# lofisampler.net
KiCad netlist of a schematic drawn in EAGLE
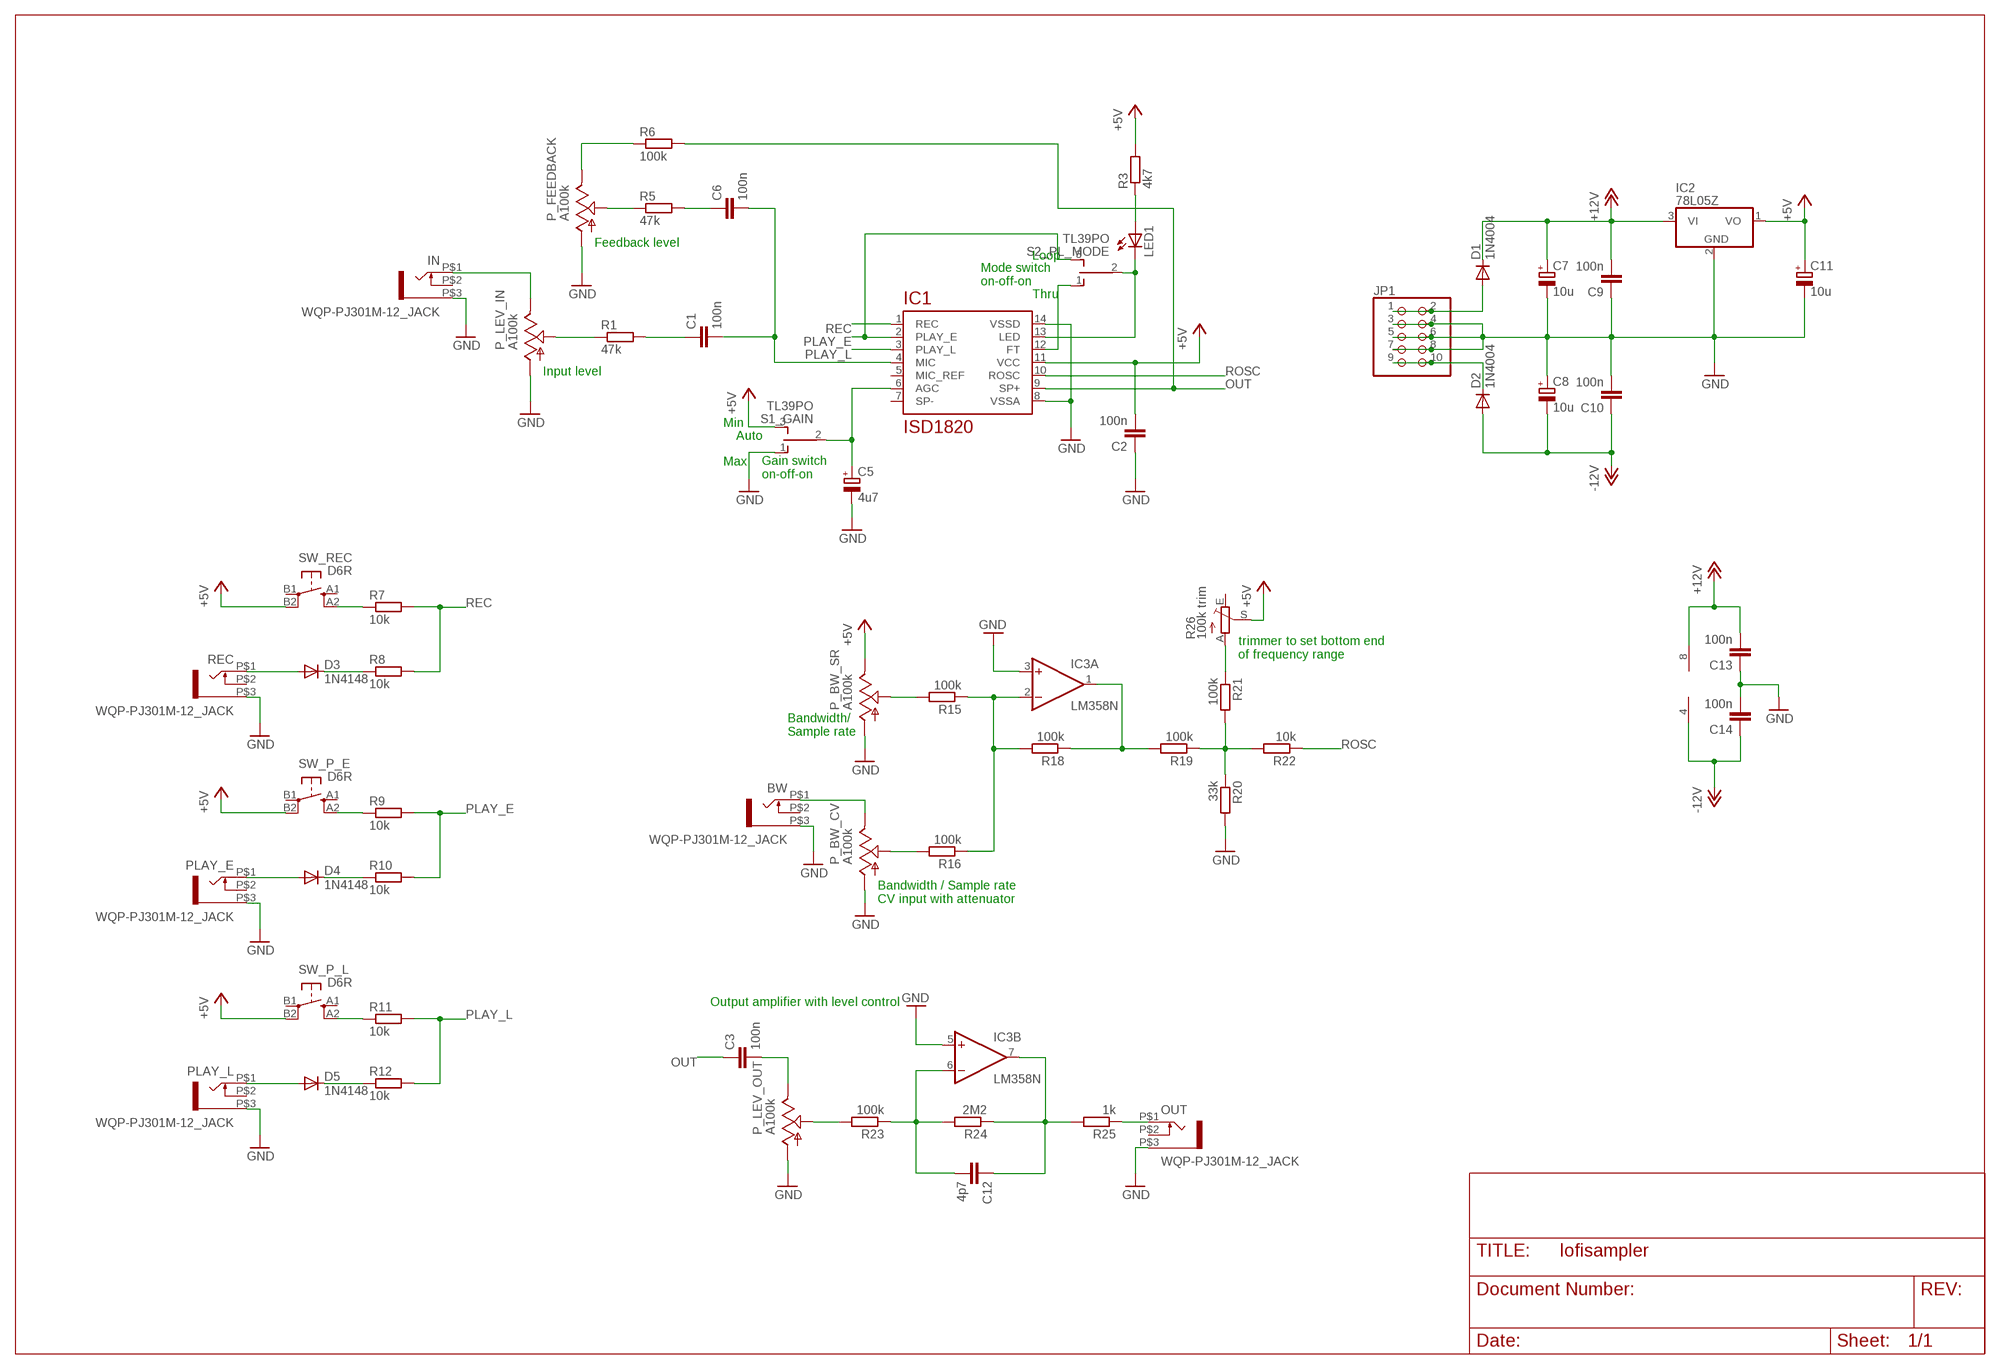
[diagram p0: schematic, sheet 1]

(export (version "E")
  (design (tool "Eeschema 10.0.6"))
  (components
    (comp (ref "BW")
      (value "WQP-PJ301M-12_JACK")
      (footprint "eagle-import:WQP-PJ301M-12_JACK")
      (libsource (lib "eagle-import") (part "WQP-PJ301M-12_JACK"))
    )
    (comp (ref "C1")
      (value "100n")
      (footprint "eagle-import:C050-025X075")
      (libsource (lib "eagle-import") (part "C-EU050-025X075"))
    )
    (comp (ref "C2")
      (value "100n")
      (footprint "eagle-import:C025-025X050")
      (libsource (lib "eagle-import") (part "C-EU025-025X050"))
    )
    (comp (ref "C3")
      (value "100n")
      (footprint "eagle-import:C050-025X075")
      (libsource (lib "eagle-import") (part "C-EU050-025X075"))
    )
    (comp (ref "C5")
      (value "4u7")
      (footprint "eagle-import:E2,5-5")
      (libsource (lib "eagle-import") (part "CPOL-EUE2.5-5"))
    )
    (comp (ref "C6")
      (value "100n")
      (footprint "eagle-import:C050-025X075")
      (libsource (lib "eagle-import") (part "C-EU050-025X075"))
    )
    (comp (ref "C7")
      (value "10u")
      (footprint "eagle-import:E2,5-5")
      (libsource (lib "eagle-import") (part "CPOL-EUE2.5-5"))
    )
    (comp (ref "C8")
      (value "10u")
      (footprint "eagle-import:E2,5-5")
      (libsource (lib "eagle-import") (part "CPOL-EUE2.5-5"))
    )
    (comp (ref "C9")
      (value "100n")
      (footprint "eagle-import:C025-025X050")
      (libsource (lib "eagle-import") (part "C-EU025-025X050"))
    )
    (comp (ref "C10")
      (value "100n")
      (footprint "eagle-import:C025-025X050")
      (libsource (lib "eagle-import") (part "C-EU025-025X050"))
    )
    (comp (ref "C11")
      (value "10u")
      (footprint "eagle-import:E2,5-5")
      (libsource (lib "eagle-import") (part "CPOL-EUE2.5-5"))
    )
    (comp (ref "C12")
      (value "4p7")
      (footprint "eagle-import:C025-025X050")
      (libsource (lib "eagle-import") (part "C-EU025-025X050"))
    )
    (comp (ref "C13")
      (value "100n")
      (footprint "eagle-import:C025-025X050")
      (libsource (lib "eagle-import") (part "C-EU025-025X050"))
    )
    (comp (ref "C14")
      (value "100n")
      (footprint "eagle-import:C025-025X050")
      (libsource (lib "eagle-import") (part "C-EU025-025X050"))
    )
    (comp (ref "D1")
      (value "1N4004")
      (footprint "eagle-import:DO41-10")
      (libsource (lib "eagle-import") (part "1N4004"))
    )
    (comp (ref "D2")
      (value "1N4004")
      (footprint "eagle-import:DO41-10")
      (libsource (lib "eagle-import") (part "1N4004"))
    )
    (comp (ref "D3")
      (value "1N4148")
      (footprint "eagle-import:DO35-7")
      (libsource (lib "eagle-import") (part "1N4148DO35-7"))
    )
    (comp (ref "D4")
      (value "1N4148")
      (footprint "eagle-import:DO35-7")
      (libsource (lib "eagle-import") (part "1N4148DO35-7"))
    )
    (comp (ref "D5")
      (value "1N4148")
      (footprint "eagle-import:DO35-7")
      (libsource (lib "eagle-import") (part "1N4148DO35-7"))
    )
    (comp (ref "IC1")
      (value "ISD1820")
      (footprint "eagle-import:DIL14")
      (libsource (lib "eagle-import") (part "ISD1820"))
    )
    (comp (ref "IC2")
      (value "78L05Z")
      (footprint "eagle-import:TO92")
      (libsource (lib "eagle-import") (part "78ZL05"))
    )
    (comp (ref "IC3")
      (value "LM358N")
      (footprint "eagle-import:DIL08")
      (libsource (lib "eagle-import") (part "LM358N"))
    )
    (comp (ref "IN")
      (value "WQP-PJ301M-12_JACK")
      (footprint "eagle-import:WQP-PJ301M-12_JACK")
      (libsource (lib "eagle-import") (part "WQP-PJ301M-12_JACK"))
    )
    (comp (ref "JP1")
      (value "PINHD-2X5")
      (footprint "eagle-import:2X05")
      (libsource (lib "eagle-import") (part "PINHD-2X5"))
    )
    (comp (ref "LED1")
      (value "LED5MM")
      (footprint "eagle-import:LED5MM")
      (libsource (lib "eagle-import") (part "LED5MM"))
    )
    (comp (ref "OUT")
      (value "WQP-PJ301M-12_JACK")
      (footprint "eagle-import:WQP-PJ301M-12_JACK")
      (libsource (lib "eagle-import") (part "WQP-PJ301M-12_JACK"))
    )
    (comp (ref "PLAY_E")
      (value "WQP-PJ301M-12_JACK")
      (footprint "eagle-import:WQP-PJ301M-12_JACK")
      (libsource (lib "eagle-import") (part "WQP-PJ301M-12_JACK"))
    )
    (comp (ref "PLAY_L")
      (value "WQP-PJ301M-12_JACK")
      (footprint "eagle-import:WQP-PJ301M-12_JACK")
      (libsource (lib "eagle-import") (part "WQP-PJ301M-12_JACK"))
    )
    (comp (ref "P_BW_CV")
      (value "A100k")
      (footprint "eagle-import:ALPS_POT_VERTICAL")
      (libsource (lib "eagle-import") (part "POT_USVERTICAL"))
    )
    (comp (ref "P_BW_SR")
      (value "A100k")
      (footprint "eagle-import:ALPS_POT_VERTICAL")
      (libsource (lib "eagle-import") (part "POT_USVERTICAL"))
    )
    (comp (ref "P_FEEDBACK")
      (value "A100k")
      (footprint "eagle-import:ALPS_POT_VERTICAL")
      (libsource (lib "eagle-import") (part "POT_USVERTICAL"))
    )
    (comp (ref "P_LEV_IN")
      (value "A100k")
      (footprint "eagle-import:ALPS_POT_VERTICAL")
      (libsource (lib "eagle-import") (part "POT_USVERTICAL"))
    )
    (comp (ref "P_LEV_OUT")
      (value "A100k")
      (footprint "eagle-import:ALPS_POT_VERTICAL")
      (libsource (lib "eagle-import") (part "POT_USVERTICAL"))
    )
    (comp (ref "R1")
      (value "47k")
      (footprint "eagle-import:0207_2V")
      (libsource (lib "eagle-import") (part "R-EU_0207/2V"))
    )
    (comp (ref "R3")
      (value "4k7")
      (footprint "eagle-import:0207_2V")
      (libsource (lib "eagle-import") (part "R-EU_0207/2V"))
    )
    (comp (ref "R5")
      (value "47k")
      (footprint "eagle-import:0207_2V")
      (libsource (lib "eagle-import") (part "R-EU_0207/2V"))
    )
    (comp (ref "R6")
      (value "100k")
      (footprint "eagle-import:0207_2V")
      (libsource (lib "eagle-import") (part "R-EU_0207/2V"))
    )
    (comp (ref "R7")
      (value "10k")
      (footprint "eagle-import:0207_2V")
      (libsource (lib "eagle-import") (part "R-EU_0207/2V"))
    )
    (comp (ref "R8")
      (value "10k")
      (footprint "eagle-import:0207_2V")
      (libsource (lib "eagle-import") (part "R-EU_0207/2V"))
    )
    (comp (ref "R9")
      (value "10k")
      (footprint "eagle-import:0207_2V")
      (libsource (lib "eagle-import") (part "R-EU_0207/2V"))
    )
    (comp (ref "R10")
      (value "10k")
      (footprint "eagle-import:0207_2V")
      (libsource (lib "eagle-import") (part "R-EU_0207/2V"))
    )
    (comp (ref "R11")
      (value "10k")
      (footprint "eagle-import:0207_2V")
      (libsource (lib "eagle-import") (part "R-EU_0207/2V"))
    )
    (comp (ref "R12")
      (value "10k")
      (footprint "eagle-import:0207_2V")
      (libsource (lib "eagle-import") (part "R-EU_0207/2V"))
    )
    (comp (ref "R15")
      (value "100k")
      (footprint "eagle-import:0207_2V")
      (libsource (lib "eagle-import") (part "R-EU_0207/2V"))
    )
    (comp (ref "R16")
      (value "100k")
      (footprint "eagle-import:0207_2V")
      (libsource (lib "eagle-import") (part "R-EU_0207/2V"))
    )
    (comp (ref "R18")
      (value "100k")
      (footprint "eagle-import:0207_2V")
      (libsource (lib "eagle-import") (part "R-EU_0207/2V"))
    )
    (comp (ref "R19")
      (value "100k")
      (footprint "eagle-import:0207_2V")
      (libsource (lib "eagle-import") (part "R-EU_0207/2V"))
    )
    (comp (ref "R20")
      (value "33k")
      (footprint "eagle-import:0207_2V")
      (libsource (lib "eagle-import") (part "R-EU_0207/2V"))
    )
    (comp (ref "R21")
      (value "100k")
      (footprint "eagle-import:0207_2V")
      (libsource (lib "eagle-import") (part "R-EU_0207/2V"))
    )
    (comp (ref "R22")
      (value "10k")
      (footprint "eagle-import:0207_2V")
      (libsource (lib "eagle-import") (part "R-EU_0207/2V"))
    )
    (comp (ref "R23")
      (value "100k")
      (footprint "eagle-import:0207_2V")
      (libsource (lib "eagle-import") (part "R-EU_0207/2V"))
    )
    (comp (ref "R24")
      (value "2M2")
      (footprint "eagle-import:0207_2V")
      (libsource (lib "eagle-import") (part "R-EU_0207/2V"))
    )
    (comp (ref "R25")
      (value "1k")
      (footprint "eagle-import:0207_2V")
      (libsource (lib "eagle-import") (part "R-EU_0207/2V"))
    )
    (comp (ref "R26")
      (value "100k trim")
      (footprint "eagle-import:B25P")
      (libsource (lib "eagle-import") (part "TRIM_EU-B25P"))
    )
    (comp (ref "REC")
      (value "WQP-PJ301M-12_JACK")
      (footprint "eagle-import:WQP-PJ301M-12_JACK")
      (libsource (lib "eagle-import") (part "WQP-PJ301M-12_JACK"))
    )
    (comp (ref "S1_GAIN")
      (value "TL39PO")
      (footprint "eagle-import:TL3XPO")
      (libsource (lib "eagle-import") (part "TL39PO"))
    )
    (comp (ref "S2_PL_MODE")
      (value "TL39PO")
      (footprint "eagle-import:TL3XPO")
      (libsource (lib "eagle-import") (part "TL39PO"))
    )
    (comp (ref "SW_P_E")
      (value "D6R")
      (footprint "eagle-import:D6R")
      (libsource (lib "eagle-import") (part "D6R"))
    )
    (comp (ref "SW_P_L")
      (value "D6R")
      (footprint "eagle-import:D6R")
      (libsource (lib "eagle-import") (part "D6R"))
    )
    (comp (ref "SW_REC")
      (value "D6R")
      (footprint "eagle-import:D6R")
      (libsource (lib "eagle-import") (part "D6R"))
    )
  )
  (nets
    (net (code "1") (name "+5V") (class "Default")
      (node (ref "C11") (pin "+") (pinfunction "+_+") (pintype "passive"))
      (node (ref "C2") (pin "2") (pinfunction "2_2") (pintype "passive"))
      (node (ref "IC1") (pin "11") (pinfunction "VCC_11") (pintype "power_in"))
      (node (ref "IC2") (pin "1") (pinfunction "VO_1") (pintype "passive"))
      (node (ref "P_BW_SR") (pin "P$1") (pinfunction "E_P$1") (pintype "passive"))
      (node (ref "R26") (pin "S") (pinfunction "S_S") (pintype "passive"))
      (node (ref "R3") (pin "2") (pinfunction "2_2") (pintype "passive"))
      (node (ref "S1_GAIN") (pin "3") (pinfunction "S_3") (pintype "passive"))
      (node (ref "SW_P_E") (pin "B2") (pinfunction "P1_B2") (pintype "passive"))
      (node (ref "SW_P_L") (pin "B2") (pinfunction "P1_B2") (pintype "passive"))
      (node (ref "SW_REC") (pin "B2") (pinfunction "P1_B2") (pintype "passive"))
    )
    (net (code "2") (name "+12V") (class "Default")
      (node (ref "C13") (pin "2") (pinfunction "2_2") (pintype "passive"))
      (node (ref "C7") (pin "+") (pinfunction "+_+") (pintype "passive"))
      (node (ref "C9") (pin "2") (pinfunction "2_2") (pintype "passive"))
      (node (ref "D1") (pin "C") (pinfunction "C_C") (pintype "passive"))
      (node (ref "IC2") (pin "3") (pinfunction "VI_3") (pintype "input"))
      (node (ref "IC3") (pin "8") (pinfunction "V+_8") (pintype "power_in"))
    )
    (net (code "3") (name "-12V") (class "Default")
      (node (ref "C10") (pin "1") (pinfunction "1_1") (pintype "passive"))
      (node (ref "C14") (pin "1") (pinfunction "1_1") (pintype "passive"))
      (node (ref "C8") (pin "-") (pinfunction "-_-") (pintype "passive"))
      (node (ref "D2") (pin "A") (pinfunction "A_A") (pintype "passive"))
      (node (ref "IC3") (pin "4") (pinfunction "V-_4") (pintype "power_in"))
    )
    (net (code "4") (name "/OUT") (class "Default")
      (node (ref "C3") (pin "1") (pinfunction "1_1") (pintype "passive"))
      (node (ref "IC1") (pin "9") (pinfunction "SP+_9") (pintype "bidirectional"))
      (node (ref "R6") (pin "2") (pinfunction "2_2") (pintype "passive"))
    )
    (net (code "5") (name "/PLAY_E") (class "Default")
      (node (ref "IC1") (pin "2") (pinfunction "PLAY_E_2") (pintype "bidirectional"))
      (node (ref "R10") (pin "2") (pinfunction "2_2") (pintype "passive"))
      (node (ref "R9") (pin "2") (pinfunction "2_2") (pintype "passive"))
      (node (ref "S2_PL_MODE") (pin "3") (pinfunction "S_3") (pintype "passive"))
    )
    (net (code "6") (name "/PLAY_L") (class "Default")
      (node (ref "IC1") (pin "3") (pinfunction "PLAY_L_3") (pintype "bidirectional"))
      (node (ref "R11") (pin "2") (pinfunction "2_2") (pintype "passive"))
      (node (ref "R12") (pin "2") (pinfunction "2_2") (pintype "passive"))
    )
    (net (code "7") (name "/REC") (class "Default")
      (node (ref "IC1") (pin "1") (pinfunction "REC_1") (pintype "bidirectional"))
      (node (ref "R7") (pin "2") (pinfunction "2_2") (pintype "passive"))
      (node (ref "R8") (pin "2") (pinfunction "2_2") (pintype "passive"))
    )
    (net (code "8") (name "/ROSC") (class "Default")
      (node (ref "IC1") (pin "10") (pinfunction "ROSC_10") (pintype "bidirectional"))
      (node (ref "R22") (pin "1") (pinfunction "1_1") (pintype "passive"))
    )
    (net (code "9") (name "GND") (class "Default")
      (node (ref "BW") (pin "P$3") (pinfunction "1_P$3") (pintype "passive"))
      (node (ref "C10") (pin "2") (pinfunction "2_2") (pintype "passive"))
      (node (ref "C11") (pin "-") (pinfunction "-_-") (pintype "passive"))
      (node (ref "C13") (pin "1") (pinfunction "1_1") (pintype "passive"))
      (node (ref "C14") (pin "2") (pinfunction "2_2") (pintype "passive"))
      (node (ref "C2") (pin "1") (pinfunction "1_1") (pintype "passive"))
      (node (ref "C5") (pin "-") (pinfunction "-_-") (pintype "passive"))
      (node (ref "C7") (pin "-") (pinfunction "-_-") (pintype "passive"))
      (node (ref "C8") (pin "+") (pinfunction "+_+") (pintype "passive"))
      (node (ref "C9") (pin "1") (pinfunction "1_1") (pintype "passive"))
      (node (ref "IC1") (pin "14") (pinfunction "VSSD_14") (pintype "power_in"))
      (node (ref "IC1") (pin "8") (pinfunction "VSSA_8") (pintype "power_in"))
      (node (ref "IC2") (pin "2") (pinfunction "GND_2") (pintype "passive"))
      (node (ref "IC3") (pin "3") (pinfunction "+IN_3") (pintype "input"))
      (node (ref "IC3") (pin "5") (pinfunction "+IN_5") (pintype "input"))
      (node (ref "IN") (pin "P$3") (pinfunction "1_P$3") (pintype "passive"))
      (node (ref "JP1") (pin "3") (pinfunction "3_3") (pintype "passive"))
      (node (ref "JP1") (pin "4") (pinfunction "4_4") (pintype "passive"))
      (node (ref "JP1") (pin "5") (pinfunction "5_5") (pintype "passive"))
      (node (ref "JP1") (pin "6") (pinfunction "6_6") (pintype "passive"))
      (node (ref "JP1") (pin "7") (pinfunction "7_7") (pintype "passive"))
      (node (ref "JP1") (pin "8") (pinfunction "8_8") (pintype "passive"))
      (node (ref "OUT") (pin "P$3") (pinfunction "1_P$3") (pintype "passive"))
      (node (ref "PLAY_E") (pin "P$3") (pinfunction "1_P$3") (pintype "passive"))
      (node (ref "PLAY_L") (pin "P$3") (pinfunction "1_P$3") (pintype "passive"))
      (node (ref "P_BW_CV") (pin "P$3") (pinfunction "A_P$3") (pintype "passive"))
      (node (ref "P_BW_SR") (pin "P$3") (pinfunction "A_P$3") (pintype "passive"))
      (node (ref "P_FEEDBACK") (pin "P$3") (pinfunction "A_P$3") (pintype "passive"))
      (node (ref "P_LEV_IN") (pin "P$3") (pinfunction "A_P$3") (pintype "passive"))
      (node (ref "P_LEV_OUT") (pin "P$3") (pinfunction "A_P$3") (pintype "passive"))
      (node (ref "R20") (pin "2") (pinfunction "2_2") (pintype "passive"))
      (node (ref "REC") (pin "P$3") (pinfunction "1_P$3") (pintype "passive"))
      (node (ref "S1_GAIN") (pin "1") (pinfunction "O_1") (pintype "passive"))
    )
    (net (code "10") (name "Net-(BW-2)") (class "Default")
      (node (ref "BW") (pin "P$1") (pinfunction "2_P$1") (pintype "passive"))
      (node (ref "P_BW_CV") (pin "P$1") (pinfunction "E_P$1") (pintype "passive"))
    )
    (net (code "11") (name "Net-(C1-Pad1)") (class "Default")
      (node (ref "C1") (pin "1") (pinfunction "1_1") (pintype "passive"))
      (node (ref "R1") (pin "2") (pinfunction "2_2") (pintype "passive"))
    )
    (net (code "12") (name "Net-(C6-Pad1)") (class "Default")
      (node (ref "C6") (pin "1") (pinfunction "1_1") (pintype "passive"))
      (node (ref "R5") (pin "2") (pinfunction "2_2") (pintype "passive"))
    )
    (net (code "13") (name "Net-(D1-PadA)") (class "Default")
      (node (ref "D1") (pin "A") (pinfunction "A_A") (pintype "passive"))
      (node (ref "JP1") (pin "1") (pinfunction "1_1") (pintype "passive"))
      (node (ref "JP1") (pin "2") (pinfunction "2_2") (pintype "passive"))
    )
    (net (code "14") (name "Net-(D2-PadC)") (class "Default")
      (node (ref "D2") (pin "C") (pinfunction "C_C") (pintype "passive"))
      (node (ref "JP1") (pin "10") (pinfunction "10_10") (pintype "passive"))
      (node (ref "JP1") (pin "9") (pinfunction "9_9") (pintype "passive"))
    )
    (net (code "15") (name "Net-(D3-PadC)") (class "Default")
      (node (ref "D3") (pin "C") (pinfunction "C_C") (pintype "passive"))
      (node (ref "R8") (pin "1") (pinfunction "1_1") (pintype "passive"))
    )
    (net (code "16") (name "Net-(D4-PadC)") (class "Default")
      (node (ref "D4") (pin "C") (pinfunction "C_C") (pintype "passive"))
      (node (ref "R10") (pin "1") (pinfunction "1_1") (pintype "passive"))
    )
    (net (code "17") (name "Net-(D5-PadC)") (class "Default")
      (node (ref "D5") (pin "C") (pinfunction "C_C") (pintype "passive"))
      (node (ref "R12") (pin "1") (pinfunction "1_1") (pintype "passive"))
    )
    (net (code "18") (name "Net-(IC1-AGC)") (class "Default")
      (node (ref "C5") (pin "+") (pinfunction "+_+") (pintype "passive"))
      (node (ref "IC1") (pin "6") (pinfunction "AGC_6") (pintype "bidirectional"))
      (node (ref "S1_GAIN") (pin "2") (pinfunction "P_2") (pintype "passive"))
    )
    (net (code "19") (name "Net-(IC1-FT)") (class "Default")
      (node (ref "IC1") (pin "12") (pinfunction "FT_12") (pintype "bidirectional"))
      (node (ref "S2_PL_MODE") (pin "1") (pinfunction "O_1") (pintype "passive"))
    )
    (net (code "20") (name "Net-(IC1-LED)") (class "Default")
      (node (ref "IC1") (pin "13") (pinfunction "LED_13") (pintype "bidirectional"))
      (node (ref "LED1") (pin "K") (pinfunction "C_K") (pintype "passive"))
      (node (ref "S2_PL_MODE") (pin "2") (pinfunction "P_2") (pintype "passive"))
    )
    (net (code "21") (name "Net-(IC1-MIC)") (class "Default")
      (node (ref "C1") (pin "2") (pinfunction "2_2") (pintype "passive"))
      (node (ref "C6") (pin "2") (pinfunction "2_2") (pintype "passive"))
      (node (ref "IC1") (pin "4") (pinfunction "MIC_4") (pintype "bidirectional"))
    )
    (net (code "22") (name "Net-(IC3A--IN)") (class "Default")
      (node (ref "IC3") (pin "2") (pinfunction "-IN_2") (pintype "input"))
      (node (ref "R15") (pin "1") (pinfunction "1_1") (pintype "passive"))
      (node (ref "R16") (pin "1") (pinfunction "1_1") (pintype "passive"))
      (node (ref "R18") (pin "2") (pinfunction "2_2") (pintype "passive"))
    )
    (net (code "23") (name "Net-(IC3A-OUT)") (class "Default")
      (node (ref "IC3") (pin "1") (pinfunction "OUT_1") (pintype "output"))
      (node (ref "R18") (pin "1") (pinfunction "1_1") (pintype "passive"))
      (node (ref "R19") (pin "2") (pinfunction "2_2") (pintype "passive"))
    )
    (net (code "24") (name "Net-(IC3B--IN)") (class "Default")
      (node (ref "C12") (pin "2") (pinfunction "2_2") (pintype "passive"))
      (node (ref "IC3") (pin "6") (pinfunction "-IN_6") (pintype "input"))
      (node (ref "R23") (pin "1") (pinfunction "1_1") (pintype "passive"))
      (node (ref "R24") (pin "2") (pinfunction "2_2") (pintype "passive"))
    )
    (net (code "25") (name "Net-(IC3B-OUT)") (class "Default")
      (node (ref "C12") (pin "1") (pinfunction "1_1") (pintype "passive"))
      (node (ref "IC3") (pin "7") (pinfunction "OUT_7") (pintype "output"))
      (node (ref "R24") (pin "1") (pinfunction "1_1") (pintype "passive"))
      (node (ref "R25") (pin "2") (pinfunction "2_2") (pintype "passive"))
    )
    (net (code "26") (name "Net-(IN-2)") (class "Default")
      (node (ref "IN") (pin "P$1") (pinfunction "2_P$1") (pintype "passive"))
      (node (ref "P_LEV_IN") (pin "P$1") (pinfunction "E_P$1") (pintype "passive"))
    )
    (net (code "27") (name "Net-(LED1-PadA)") (class "Default")
      (node (ref "LED1") (pin "A") (pinfunction "A_A") (pintype "passive"))
      (node (ref "R3") (pin "1") (pinfunction "1_1") (pintype "passive"))
    )
    (net (code "28") (name "Net-(OUT-2)") (class "Default")
      (node (ref "OUT") (pin "P$1") (pinfunction "2_P$1") (pintype "passive"))
      (node (ref "R25") (pin "1") (pinfunction "1_1") (pintype "passive"))
    )
    (net (code "29") (name "Net-(PLAY_E-2)") (class "Default")
      (node (ref "D4") (pin "A") (pinfunction "A_A") (pintype "passive"))
      (node (ref "PLAY_E") (pin "P$1") (pinfunction "2_P$1") (pintype "passive"))
    )
    (net (code "30") (name "Net-(PLAY_L-2)") (class "Default")
      (node (ref "D5") (pin "A") (pinfunction "A_A") (pintype "passive"))
      (node (ref "PLAY_L") (pin "P$1") (pinfunction "2_P$1") (pintype "passive"))
    )
    (net (code "31") (name "Net-(P_BW_CV-S)") (class "Default")
      (node (ref "P_BW_CV") (pin "P$2") (pinfunction "S_P$2") (pintype "passive"))
      (node (ref "R16") (pin "2") (pinfunction "2_2") (pintype "passive"))
    )
    (net (code "32") (name "Net-(P_BW_SR-S)") (class "Default")
      (node (ref "P_BW_SR") (pin "P$2") (pinfunction "S_P$2") (pintype "passive"))
      (node (ref "R15") (pin "2") (pinfunction "2_2") (pintype "passive"))
    )
    (net (code "33") (name "Net-(P_FEEDBACK-E)") (class "Default")
      (node (ref "P_FEEDBACK") (pin "P$1") (pinfunction "E_P$1") (pintype "passive"))
      (node (ref "R6") (pin "1") (pinfunction "1_1") (pintype "passive"))
    )
    (net (code "34") (name "Net-(P_FEEDBACK-S)") (class "Default")
      (node (ref "P_FEEDBACK") (pin "P$2") (pinfunction "S_P$2") (pintype "passive"))
      (node (ref "R5") (pin "1") (pinfunction "1_1") (pintype "passive"))
    )
    (net (code "35") (name "Net-(P_LEV_IN-S)") (class "Default")
      (node (ref "P_LEV_IN") (pin "P$2") (pinfunction "S_P$2") (pintype "passive"))
      (node (ref "R1") (pin "1") (pinfunction "1_1") (pintype "passive"))
    )
    (net (code "36") (name "Net-(P_LEV_OUT-E)") (class "Default")
      (node (ref "C3") (pin "2") (pinfunction "2_2") (pintype "passive"))
      (node (ref "P_LEV_OUT") (pin "P$1") (pinfunction "E_P$1") (pintype "passive"))
    )
    (net (code "37") (name "Net-(P_LEV_OUT-S)") (class "Default")
      (node (ref "P_LEV_OUT") (pin "P$2") (pinfunction "S_P$2") (pintype "passive"))
      (node (ref "R23") (pin "2") (pinfunction "2_2") (pintype "passive"))
    )
    (net (code "38") (name "Net-(R19-Pad1)") (class "Default")
      (node (ref "R19") (pin "1") (pinfunction "1_1") (pintype "passive"))
      (node (ref "R20") (pin "1") (pinfunction "1_1") (pintype "passive"))
      (node (ref "R21") (pin "2") (pinfunction "2_2") (pintype "passive"))
      (node (ref "R22") (pin "2") (pinfunction "2_2") (pintype "passive"))
    )
    (net (code "39") (name "Net-(R21-Pad1)") (class "Default")
      (node (ref "R21") (pin "1") (pinfunction "1_1") (pintype "passive"))
      (node (ref "R26") (pin "A") (pinfunction "A_A") (pintype "passive"))
    )
    (net (code "40") (name "Net-(REC-2)") (class "Default")
      (node (ref "D3") (pin "A") (pinfunction "A_A") (pintype "passive"))
      (node (ref "REC") (pin "P$1") (pinfunction "2_P$1") (pintype "passive"))
    )
    (net (code "41") (name "Net-(SW_P_E-S1)") (class "Default")
      (node (ref "R9") (pin "1") (pinfunction "1_1") (pintype "passive"))
      (node (ref "SW_P_E") (pin "A2") (pinfunction "S1_A2") (pintype "passive"))
    )
    (net (code "42") (name "Net-(SW_P_L-S1)") (class "Default")
      (node (ref "R11") (pin "1") (pinfunction "1_1") (pintype "passive"))
      (node (ref "SW_P_L") (pin "A2") (pinfunction "S1_A2") (pintype "passive"))
    )
    (net (code "43") (name "Net-(SW_REC-S1)") (class "Default")
      (node (ref "R7") (pin "1") (pinfunction "1_1") (pintype "passive"))
      (node (ref "SW_REC") (pin "A2") (pinfunction "S1_A2") (pintype "passive"))
    )
    (net (code "44") (name "unconnected-(BW-3-PadP$2)") (class "Default")
      (node (ref "BW") (pin "P$2") (pinfunction "3_P$2") (pintype "passive"))
    )
    (net (code "45") (name "unconnected-(IC1-MIC_REF-Pad5)") (class "Default")
      (node (ref "IC1") (pin "5") (pinfunction "MIC_REF_5") (pintype "bidirectional"))
    )
    (net (code "46") (name "unconnected-(IC1-SP--Pad7)") (class "Default")
      (node (ref "IC1") (pin "7") (pinfunction "SP-_7") (pintype "bidirectional"))
    )
    (net (code "47") (name "unconnected-(IN-3-PadP$2)") (class "Default")
      (node (ref "IN") (pin "P$2") (pinfunction "3_P$2") (pintype "passive"))
    )
    (net (code "48") (name "unconnected-(OUT-3-PadP$2)") (class "Default")
      (node (ref "OUT") (pin "P$2") (pinfunction "3_P$2") (pintype "passive"))
    )
    (net (code "49") (name "unconnected-(PLAY_E-3-PadP$2)") (class "Default")
      (node (ref "PLAY_E") (pin "P$2") (pinfunction "3_P$2") (pintype "passive"))
    )
    (net (code "50") (name "unconnected-(PLAY_L-3-PadP$2)") (class "Default")
      (node (ref "PLAY_L") (pin "P$2") (pinfunction "3_P$2") (pintype "passive"))
    )
    (net (code "51") (name "unconnected-(R26-PadE)") (class "Default")
      (node (ref "R26") (pin "E") (pinfunction "E_E") (pintype "passive"))
    )
    (net (code "52") (name "unconnected-(REC-3-PadP$2)") (class "Default")
      (node (ref "REC") (pin "P$2") (pinfunction "3_P$2") (pintype "passive"))
    )
    (net (code "53") (name "unconnected-(SW_P_E-P-PadB1)") (class "Default")
      (node (ref "SW_P_E") (pin "B1") (pinfunction "P_B1") (pintype "passive"))
    )
    (net (code "54") (name "unconnected-(SW_P_E-S-PadA1)") (class "Default")
      (node (ref "SW_P_E") (pin "A1") (pinfunction "S_A1") (pintype "passive"))
    )
    (net (code "55") (name "unconnected-(SW_P_L-P-PadB1)") (class "Default")
      (node (ref "SW_P_L") (pin "B1") (pinfunction "P_B1") (pintype "passive"))
    )
    (net (code "56") (name "unconnected-(SW_P_L-S-PadA1)") (class "Default")
      (node (ref "SW_P_L") (pin "A1") (pinfunction "S_A1") (pintype "passive"))
    )
    (net (code "57") (name "unconnected-(SW_REC-P-PadB1)") (class "Default")
      (node (ref "SW_REC") (pin "B1") (pinfunction "P_B1") (pintype "passive"))
    )
    (net (code "58") (name "unconnected-(SW_REC-S-PadA1)") (class "Default")
      (node (ref "SW_REC") (pin "A1") (pinfunction "S_A1") (pintype "passive"))
    )
  )
)
